# supply.net
KiCad netlist of a schematic drawn in Altium Designer
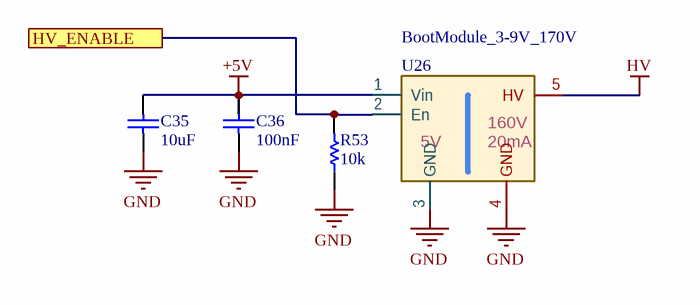
[diagram p0: supply.SchDoc]

(export (version "E")
  (design (tool "Eeschema 10.0.6"))
  (components
    (comp (ref "C35")
      (value "10uF")
      (footprint "0603_[1608]")
      (description "Capacitor")
      (libsource (lib "develer_generic") (part "Cap"))
    )
    (comp (ref "C36")
      (value "100nF")
      (footprint "0603_[1608]")
      (description "Capacitor")
      (libsource (lib "develer_generic") (part "Cap"))
    )
    (comp (ref "R53")
      (value "10k")
      (footprint "0603_[1608]")
      (description "Resistor")
      (fields (field (name "PUBLISHER") "Develer srl"))
      (libsource (lib "develer_generic") (part "Res"))
    )
    (comp (ref "U26")
      (value "BootModule_3-9V_170V")
      (footprint "BoostModule")
      (description "som boot power supply 3-9V to 170V")
      (fields (field (name "PUBLISHER") "Develer srl"))
      (libsource (lib "develer_components") (part "BootModule_3-9V_170V"))
    )
  )
  (nets
    (net (code "1") (name "+5V") (class "Default")
      (node (ref "C35") (pin "2") (pinfunction "2_2") (pintype "passive"))
      (node (ref "C36") (pin "2") (pinfunction "2_2") (pintype "passive"))
      (node (ref "U26") (pin "1") (pinfunction "Vin_1") (pintype "passive"))
    )
    (net (code "2") (name "/HV_ENABLE") (class "Default")
      (node (ref "R53") (pin "2") (pinfunction "2_2") (pintype "passive"))
      (node (ref "U26") (pin "2") (pinfunction "En_2") (pintype "passive"))
    )
    (net (code "3") (name "GND") (class "Default")
      (node (ref "C35") (pin "1") (pinfunction "1_1") (pintype "passive"))
      (node (ref "C36") (pin "1") (pinfunction "1_1") (pintype "passive"))
      (node (ref "R53") (pin "1") (pinfunction "1_1") (pintype "passive"))
      (node (ref "U26") (pin "3") (pinfunction "GND_3") (pintype "passive"))
      (node (ref "U26") (pin "4") (pinfunction "GND_4") (pintype "passive"))
    )
    (net (code "4") (name "HV") (class "Default")
      (node (ref "U26") (pin "5") (pinfunction "HV_5") (pintype "passive"))
    )
  )
)
